# ESS-BoB_-_ESS_Interface.net
KiCad netlist of a schematic drawn in Altium Designer
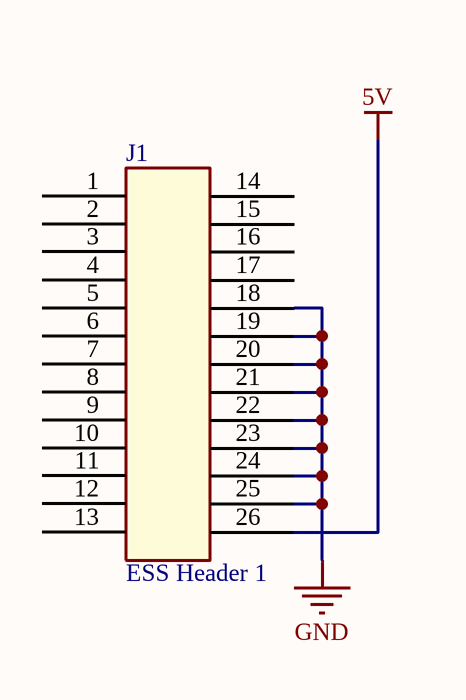
[diagram p0: ESS-BoB - ESS Interface.SchDoc]

(export (version "E")
  (design (tool "Eeschema 10.0.6"))
  (components
    (comp (ref "J1")
      (value "ESS Header 1")
      (footprint "Samtec ESQ-113-33-G-D")
      (libsource (lib "my parts library") (part "CON2x13 Alt. Numbering"))
    )
  )
  (nets
    (net (code "1") (name "5V") (class "Default")
      (node (ref "J1") (pin "26") (pinfunction "26_26") (pintype "passive"))
    )
    (net (code "2") (name "GND") (class "Default")
      (node (ref "J1") (pin "18") (pinfunction "18_18") (pintype "passive"))
      (node (ref "J1") (pin "19") (pinfunction "19_19") (pintype "passive"))
      (node (ref "J1") (pin "20") (pinfunction "20_20") (pintype "passive"))
      (node (ref "J1") (pin "21") (pinfunction "21_21") (pintype "passive"))
      (node (ref "J1") (pin "22") (pinfunction "22_22") (pintype "passive"))
      (node (ref "J1") (pin "23") (pinfunction "23_23") (pintype "passive"))
      (node (ref "J1") (pin "24") (pinfunction "24_24") (pintype "passive"))
      (node (ref "J1") (pin "25") (pinfunction "25_25") (pintype "passive"))
    )
    (net (code "3") (name "unconnected-(J1-Pad1)") (class "Default")
      (node (ref "J1") (pin "1") (pinfunction "1_1") (pintype "passive"))
    )
    (net (code "4") (name "unconnected-(J1-Pad2)") (class "Default")
      (node (ref "J1") (pin "2") (pinfunction "2_2") (pintype "passive"))
    )
    (net (code "5") (name "unconnected-(J1-Pad3)") (class "Default")
      (node (ref "J1") (pin "3") (pinfunction "3_3") (pintype "passive"))
    )
    (net (code "6") (name "unconnected-(J1-Pad4)") (class "Default")
      (node (ref "J1") (pin "4") (pinfunction "4_4") (pintype "passive"))
    )
    (net (code "7") (name "unconnected-(J1-Pad5)") (class "Default")
      (node (ref "J1") (pin "5") (pinfunction "5_5") (pintype "passive"))
    )
    (net (code "8") (name "unconnected-(J1-Pad6)") (class "Default")
      (node (ref "J1") (pin "6") (pinfunction "6_6") (pintype "passive"))
    )
    (net (code "9") (name "unconnected-(J1-Pad7)") (class "Default")
      (node (ref "J1") (pin "7") (pinfunction "7_7") (pintype "passive"))
    )
    (net (code "10") (name "unconnected-(J1-Pad8)") (class "Default")
      (node (ref "J1") (pin "8") (pinfunction "8_8") (pintype "passive"))
    )
    (net (code "11") (name "unconnected-(J1-Pad9)") (class "Default")
      (node (ref "J1") (pin "9") (pinfunction "9_9") (pintype "passive"))
    )
    (net (code "12") (name "unconnected-(J1-Pad10)") (class "Default")
      (node (ref "J1") (pin "10") (pinfunction "10_10") (pintype "passive"))
    )
    (net (code "13") (name "unconnected-(J1-Pad11)") (class "Default")
      (node (ref "J1") (pin "11") (pinfunction "11_11") (pintype "passive"))
    )
    (net (code "14") (name "unconnected-(J1-Pad12)") (class "Default")
      (node (ref "J1") (pin "12") (pinfunction "12_12") (pintype "passive"))
    )
    (net (code "15") (name "unconnected-(J1-Pad13)") (class "Default")
      (node (ref "J1") (pin "13") (pinfunction "13_13") (pintype "passive"))
    )
    (net (code "16") (name "unconnected-(J1-Pad14)") (class "Default")
      (node (ref "J1") (pin "14") (pinfunction "14_14") (pintype "passive"))
    )
    (net (code "17") (name "unconnected-(J1-Pad15)") (class "Default")
      (node (ref "J1") (pin "15") (pinfunction "15_15") (pintype "passive"))
    )
    (net (code "18") (name "unconnected-(J1-Pad16)") (class "Default")
      (node (ref "J1") (pin "16") (pinfunction "16_16") (pintype "passive"))
    )
    (net (code "19") (name "unconnected-(J1-Pad17)") (class "Default")
      (node (ref "J1") (pin "17") (pinfunction "17_17") (pintype "passive"))
    )
  )
)
